# OSSIEPSSuperCap.net
KiCad netlist of a schematic drawn in EAGLE
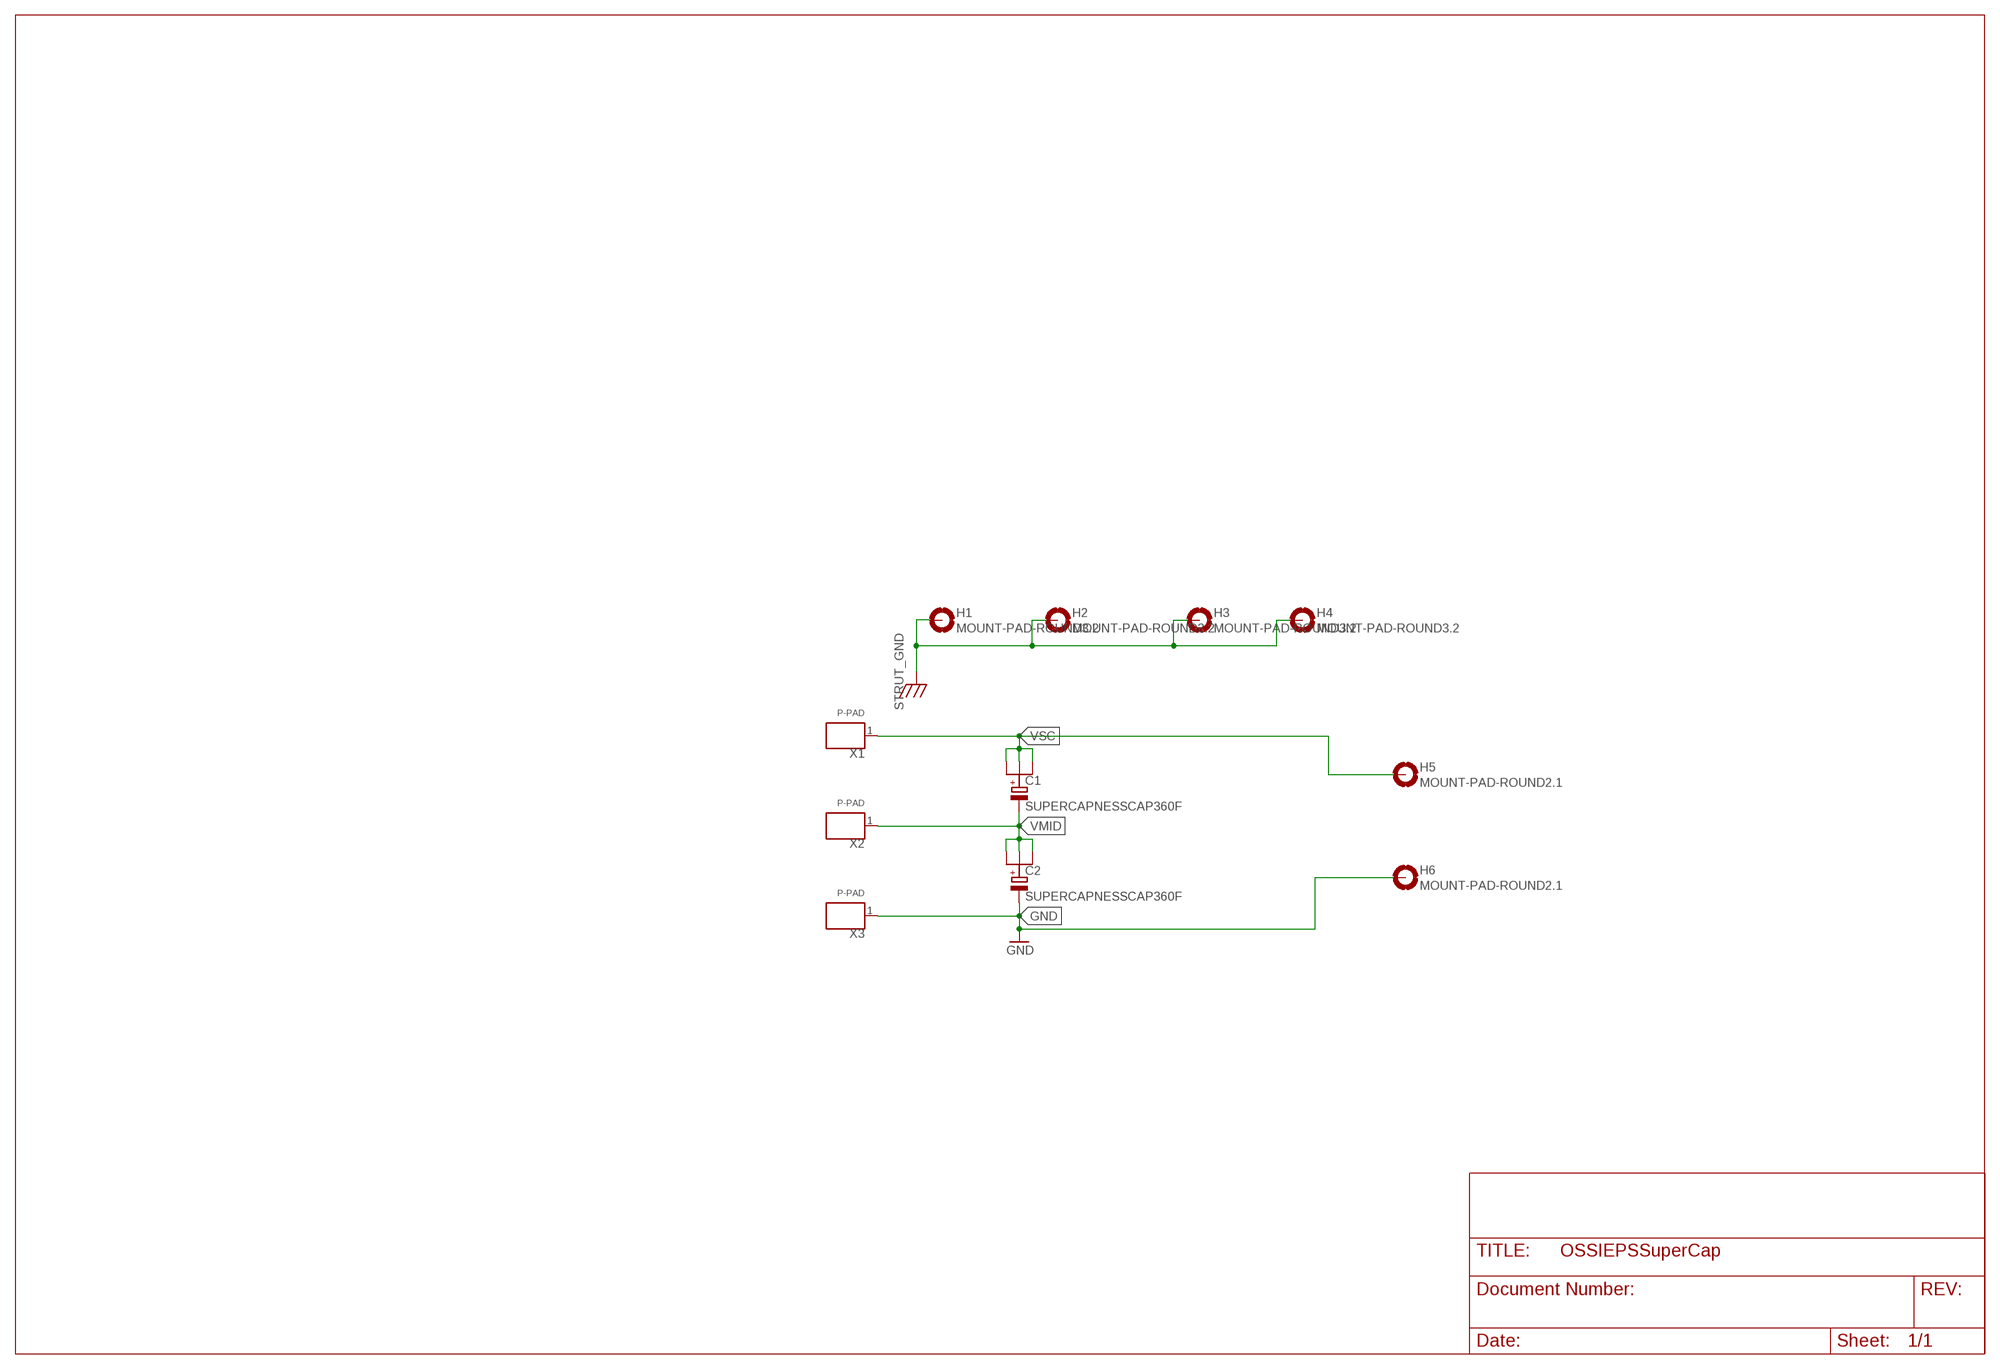
[diagram p0: schematic, sheet 1]

(export (version "E")
  (design (tool "Eeschema 10.0.6"))
  (components
    (comp (ref "C1")
      (value "SUPERCAPNESSCAP360F")
      (footprint "eagle-import:NESSCAP360F")
      (libsource (lib "eagle-import") (part "SUPERCAPNESSCAP360F"))
    )
    (comp (ref "C2")
      (value "SUPERCAPNESSCAP360F")
      (footprint "eagle-import:NESSCAP360F")
      (libsource (lib "eagle-import") (part "SUPERCAPNESSCAP360F"))
    )
    (comp (ref "H1")
      (value "MOUNT-PAD-ROUND3.2")
      (footprint "eagle-import:3.2-PAD-ROUND")
      (libsource (lib "eagle-import") (part "MOUNT-PAD-ROUND3.2"))
    )
    (comp (ref "H2")
      (value "MOUNT-PAD-ROUND3.2")
      (footprint "eagle-import:3.2-PAD-ROUND")
      (libsource (lib "eagle-import") (part "MOUNT-PAD-ROUND3.2"))
    )
    (comp (ref "H3")
      (value "MOUNT-PAD-ROUND3.2")
      (footprint "eagle-import:3.2-PAD-ROUND")
      (libsource (lib "eagle-import") (part "MOUNT-PAD-ROUND3.2"))
    )
    (comp (ref "H4")
      (value "MOUNT-PAD-ROUND3.2")
      (footprint "eagle-import:3.2-PAD-ROUND")
      (libsource (lib "eagle-import") (part "MOUNT-PAD-ROUND3.2"))
    )
    (comp (ref "H5")
      (value "MOUNT-PAD-ROUND2.1")
      (footprint "eagle-import:2.1-PAD-ROUND")
      (libsource (lib "eagle-import") (part "MOUNT-PAD-ROUND2.1"))
    )
    (comp (ref "H6")
      (value "MOUNT-PAD-ROUND2.1")
      (footprint "eagle-import:2.1-PAD-ROUND")
      (libsource (lib "eagle-import") (part "MOUNT-PAD-ROUND2.1"))
    )
    (comp (ref "X1")
      (value "P-PAD")
      (footprint "eagle-import:P-PAD")
      (libsource (lib "eagle-import") (part "P-PAD"))
    )
    (comp (ref "X2")
      (value "P-PAD")
      (footprint "eagle-import:P-PAD")
      (libsource (lib "eagle-import") (part "P-PAD"))
    )
    (comp (ref "X3")
      (value "P-PAD")
      (footprint "eagle-import:P-PAD")
      (libsource (lib "eagle-import") (part "P-PAD"))
    )
  )
  (nets
    (net (code "1") (name "GND") (class "Default")
      (node (ref "C2") (pin "N") (pinfunction "N_N") (pintype "passive"))
      (node (ref "H6") (pin "B3,2") (pinfunction "MOUNT_B3,2") (pintype "passive"))
      (node (ref "X3") (pin "1") (pinfunction "P$1_1") (pintype "bidirectional"))
    )
    (net (code "2") (name "STRUT_GND") (class "Default")
      (node (ref "H1") (pin "B3,2") (pinfunction "MOUNT_B3,2") (pintype "passive"))
      (node (ref "H2") (pin "B3,2") (pinfunction "MOUNT_B3,2") (pintype "passive"))
      (node (ref "H3") (pin "B3,2") (pinfunction "MOUNT_B3,2") (pintype "passive"))
      (node (ref "H4") (pin "B3,2") (pinfunction "MOUNT_B3,2") (pintype "passive"))
    )
    (net (code "3") (name "VMID") (class "Default")
      (node (ref "C1") (pin "N") (pinfunction "N_N") (pintype "passive"))
      (node (ref "C2") (pin "P1") (pinfunction "P1_P1") (pintype "passive"))
      (node (ref "C2") (pin "P2") (pinfunction "P2_P2") (pintype "passive"))
      (node (ref "C2") (pin "P3") (pinfunction "P3_P3") (pintype "passive"))
      (node (ref "X2") (pin "1") (pinfunction "P$1_1") (pintype "bidirectional"))
    )
    (net (code "4") (name "VSC") (class "Default")
      (node (ref "C1") (pin "P1") (pinfunction "P1_P1") (pintype "passive"))
      (node (ref "C1") (pin "P2") (pinfunction "P2_P2") (pintype "passive"))
      (node (ref "C1") (pin "P3") (pinfunction "P3_P3") (pintype "passive"))
      (node (ref "H5") (pin "B3,2") (pinfunction "MOUNT_B3,2") (pintype "passive"))
      (node (ref "X1") (pin "1") (pinfunction "P$1_1") (pintype "bidirectional"))
    )
  )
)
